# S88_Nano_16R0C_2Layers_DuPont.net
KiCad netlist of a schematic drawn in EAGLE
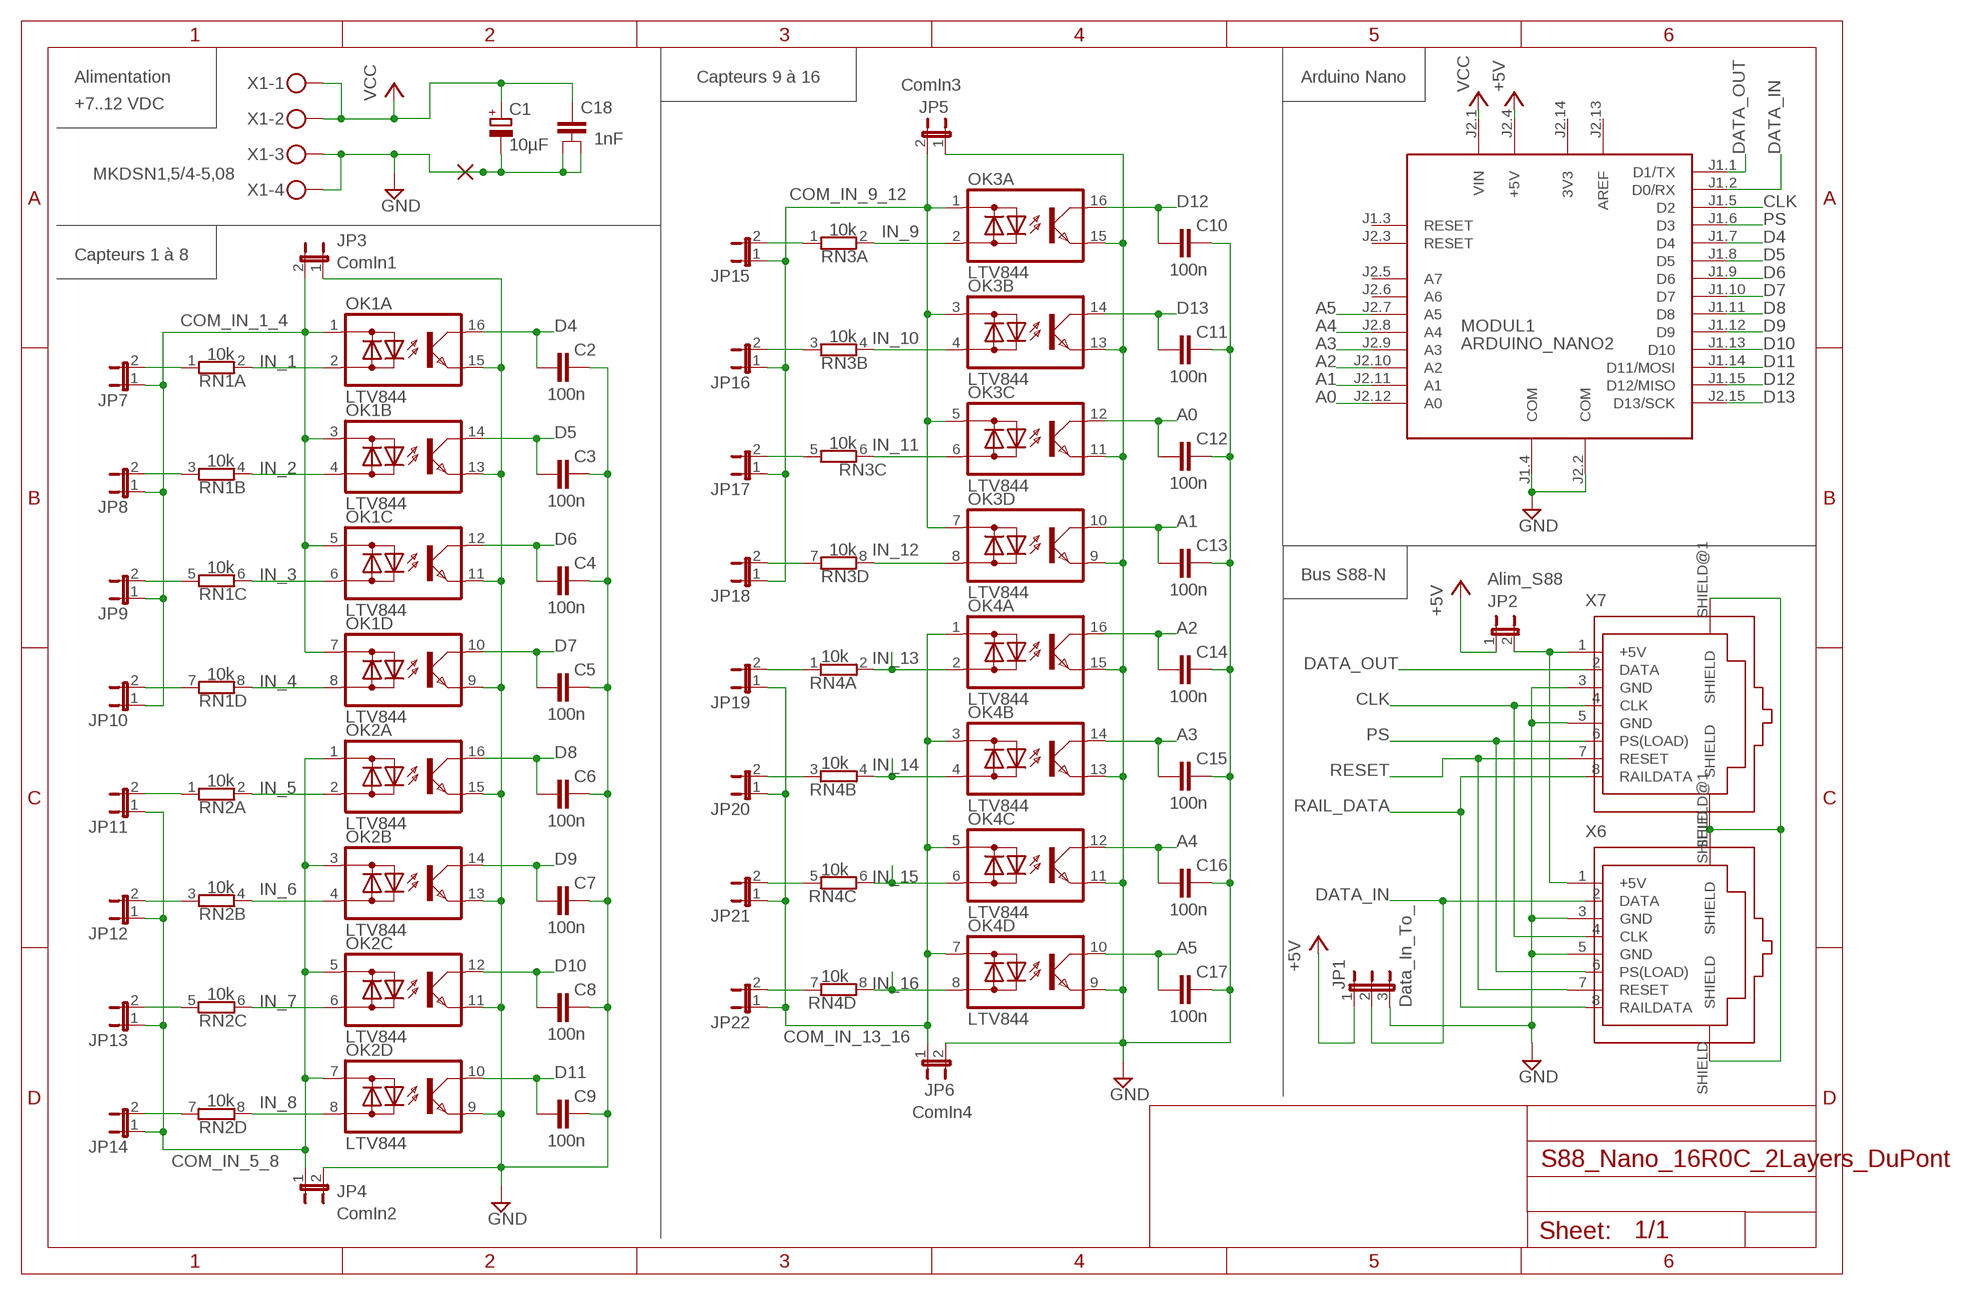
[diagram p0: schematic, sheet 1]

(export (version "E")
  (design (tool "Eeschema 10.0.6"))
  (components
    (comp (ref "C1")
      (value "10µF")
      (footprint "eagle-import:E5-6")
      (libsource (lib "eagle-import") (part "CPOL-EUE5-6"))
    )
    (comp (ref "C2")
      (value "100n")
      (footprint "eagle-import:C025-025X050")
      (libsource (lib "eagle-import") (part "C-EU025-025X050"))
    )
    (comp (ref "C3")
      (value "100n")
      (footprint "eagle-import:C025-025X050")
      (libsource (lib "eagle-import") (part "C-EU025-025X050"))
    )
    (comp (ref "C4")
      (value "100n")
      (footprint "eagle-import:C025-025X050")
      (libsource (lib "eagle-import") (part "C-EU025-025X050"))
    )
    (comp (ref "C5")
      (value "100n")
      (footprint "eagle-import:C025-025X050")
      (libsource (lib "eagle-import") (part "C-EU025-025X050"))
    )
    (comp (ref "C6")
      (value "100n")
      (footprint "eagle-import:C025-025X050")
      (libsource (lib "eagle-import") (part "C-EU025-025X050"))
    )
    (comp (ref "C7")
      (value "100n")
      (footprint "eagle-import:C025-025X050")
      (libsource (lib "eagle-import") (part "C-EU025-025X050"))
    )
    (comp (ref "C8")
      (value "100n")
      (footprint "eagle-import:C025-025X050")
      (libsource (lib "eagle-import") (part "C-EU025-025X050"))
    )
    (comp (ref "C9")
      (value "100n")
      (footprint "eagle-import:C025-025X050")
      (libsource (lib "eagle-import") (part "C-EU025-025X050"))
    )
    (comp (ref "C10")
      (value "100n")
      (footprint "eagle-import:C025-025X050")
      (libsource (lib "eagle-import") (part "C-EU025-025X050"))
    )
    (comp (ref "C11")
      (value "100n")
      (footprint "eagle-import:C025-025X050")
      (libsource (lib "eagle-import") (part "C-EU025-025X050"))
    )
    (comp (ref "C12")
      (value "100n")
      (footprint "eagle-import:C025-025X050")
      (libsource (lib "eagle-import") (part "C-EU025-025X050"))
    )
    (comp (ref "C13")
      (value "100n")
      (footprint "eagle-import:C025-025X050")
      (libsource (lib "eagle-import") (part "C-EU025-025X050"))
    )
    (comp (ref "C14")
      (value "100n")
      (footprint "eagle-import:C025-025X050")
      (libsource (lib "eagle-import") (part "C-EU025-025X050"))
    )
    (comp (ref "C15")
      (value "100n")
      (footprint "eagle-import:C025-025X050")
      (libsource (lib "eagle-import") (part "C-EU025-025X050"))
    )
    (comp (ref "C16")
      (value "100n")
      (footprint "eagle-import:C025-025X050")
      (libsource (lib "eagle-import") (part "C-EU025-025X050"))
    )
    (comp (ref "C17")
      (value "100n")
      (footprint "eagle-import:C025-025X050")
      (libsource (lib "eagle-import") (part "C-EU025-025X050"))
    )
    (comp (ref "C18")
      (value "1nF")
      (footprint "eagle-import:C025_050-024X070")
      (libsource (lib "eagle-import") (part "C-EU"))
    )
    (comp (ref "JP1")
      (value "Data_In_To_")
      (footprint "eagle-import:JP2")
      (libsource (lib "eagle-import") (part "JP2E"))
    )
    (comp (ref "JP2")
      (value "Alim_S88")
      (footprint "eagle-import:JP1")
      (libsource (lib "eagle-import") (part "JP1E"))
    )
    (comp (ref "JP3")
      (value "ComIn1")
      (footprint "eagle-import:JP1")
      (libsource (lib "eagle-import") (part "JP1E"))
    )
    (comp (ref "JP4")
      (value "ComIn2")
      (footprint "eagle-import:JP1")
      (libsource (lib "eagle-import") (part "JP1E"))
    )
    (comp (ref "JP5")
      (value "ComIn3")
      (footprint "eagle-import:JP1")
      (libsource (lib "eagle-import") (part "JP1E"))
    )
    (comp (ref "JP6")
      (value "ComIn4")
      (footprint "eagle-import:JP1")
      (libsource (lib "eagle-import") (part "JP1E"))
    )
    (comp (ref "JP7")
      (value "JP1E")
      (footprint "eagle-import:JP1")
      (libsource (lib "eagle-import") (part "jumper_252_JP1E"))
    )
    (comp (ref "JP8")
      (value "JP1E")
      (footprint "eagle-import:JP1")
      (libsource (lib "eagle-import") (part "jumper_252_JP1E"))
    )
    (comp (ref "JP9")
      (value "JP1E")
      (footprint "eagle-import:JP1")
      (libsource (lib "eagle-import") (part "jumper_252_JP1E"))
    )
    (comp (ref "JP10")
      (value "JP1E")
      (footprint "eagle-import:JP1")
      (libsource (lib "eagle-import") (part "jumper_252_JP1E"))
    )
    (comp (ref "JP11")
      (value "JP1E")
      (footprint "eagle-import:JP1")
      (libsource (lib "eagle-import") (part "jumper_252_JP1E"))
    )
    (comp (ref "JP12")
      (value "JP1E")
      (footprint "eagle-import:JP1")
      (libsource (lib "eagle-import") (part "jumper_252_JP1E"))
    )
    (comp (ref "JP13")
      (value "JP1E")
      (footprint "eagle-import:JP1")
      (libsource (lib "eagle-import") (part "jumper_252_JP1E"))
    )
    (comp (ref "JP14")
      (value "JP1E")
      (footprint "eagle-import:JP1")
      (libsource (lib "eagle-import") (part "jumper_252_JP1E"))
    )
    (comp (ref "JP15")
      (value "JP1E")
      (footprint "eagle-import:JP1")
      (libsource (lib "eagle-import") (part "jumper_252_JP1E"))
    )
    (comp (ref "JP16")
      (value "JP1E")
      (footprint "eagle-import:JP1")
      (libsource (lib "eagle-import") (part "jumper_252_JP1E"))
    )
    (comp (ref "JP17")
      (value "JP1E")
      (footprint "eagle-import:JP1")
      (libsource (lib "eagle-import") (part "jumper_252_JP1E"))
    )
    (comp (ref "JP18")
      (value "JP1E")
      (footprint "eagle-import:JP1")
      (libsource (lib "eagle-import") (part "jumper_252_JP1E"))
    )
    (comp (ref "JP19")
      (value "JP1E")
      (footprint "eagle-import:JP1")
      (libsource (lib "eagle-import") (part "jumper_252_JP1E"))
    )
    (comp (ref "JP20")
      (value "JP1E")
      (footprint "eagle-import:JP1")
      (libsource (lib "eagle-import") (part "jumper_252_JP1E"))
    )
    (comp (ref "JP21")
      (value "JP1E")
      (footprint "eagle-import:JP1")
      (libsource (lib "eagle-import") (part "jumper_252_JP1E"))
    )
    (comp (ref "JP22")
      (value "JP1E")
      (footprint "eagle-import:JP1")
      (libsource (lib "eagle-import") (part "jumper_252_JP1E"))
    )
    (comp (ref "MODUL1")
      (value "ARDUINO_NANO2")
      (footprint "eagle-import:ARDUINO_NANO2")
      (libsource (lib "eagle-import") (part "ARDUINO_NANO2"))
    )
    (comp (ref "OK1")
      (value "LTV844")
      (footprint "eagle-import:DIL16")
      (libsource (lib "eagle-import") (part "LTV844"))
    )
    (comp (ref "OK2")
      (value "LTV844")
      (footprint "eagle-import:DIL16")
      (libsource (lib "eagle-import") (part "LTV844"))
    )
    (comp (ref "OK3")
      (value "LTV844")
      (footprint "eagle-import:DIL16")
      (libsource (lib "eagle-import") (part "LTV844"))
    )
    (comp (ref "OK4")
      (value "LTV844")
      (footprint "eagle-import:DIL16")
      (libsource (lib "eagle-import") (part "LTV844"))
    )
    (comp (ref "PAD1")
      (value "1,9/0,8")
      (footprint "eagle-import:1,6_0,9")
      (libsource (lib "eagle-import") (part "1,9/0,8"))
    )
    (comp (ref "RN1")
      (value "10k")
      (footprint "eagle-import:SIL8")
      (libsource (lib "eagle-import") (part "E4R"))
    )
    (comp (ref "RN2")
      (value "10k")
      (footprint "eagle-import:SIL8")
      (libsource (lib "eagle-import") (part "E4R"))
    )
    (comp (ref "RN3")
      (value "10k")
      (footprint "eagle-import:SIL8")
      (libsource (lib "eagle-import") (part "E4R"))
    )
    (comp (ref "RN4")
      (value "10k")
      (footprint "eagle-import:SIL8")
      (libsource (lib "eagle-import") (part "E4R"))
    )
    (comp (ref "X1")
      (value "MKDSN1,5/4-5,08")
      (footprint "eagle-import:MKDSN1,5_4-5,08")
      (libsource (lib "eagle-import") (part "MKDSN1,5/4-5,08"))
    )
    (comp (ref "X6")
      (value "RJ45-SHIELDED")
      (footprint "eagle-import:RJ45-SHIELDED")
      (libsource (lib "eagle-import") (part "RJ45-SHIELDED"))
    )
    (comp (ref "X7")
      (value "RJ45-SHIELDED")
      (footprint "eagle-import:RJ45-SHIELDED")
      (libsource (lib "eagle-import") (part "RJ45-SHIELDED"))
    )
  )
  (nets
    (net (code "1") (name "+5V") (class "Default")
      (node (ref "JP1") (pin "1") (pinfunction "1_1") (pintype "passive"))
      (node (ref "JP2") (pin "1") (pinfunction "1_1") (pintype "passive"))
      (node (ref "MODUL1") (pin "J2.4") (pinfunction "+5V_J2.4") (pintype "power_in"))
    )
    (net (code "2") (name "/3V3") (class "Default")
      (node (ref "MODUL1") (pin "J2.14") (pinfunction "3V3_J2.14") (pintype "power_in"))
    )
    (net (code "3") (name "/A0") (class "Default")
      (node (ref "C12") (pin "1") (pinfunction "1_1") (pintype "passive"))
      (node (ref "MODUL1") (pin "J2.12") (pinfunction "A0_J2.12") (pintype "bidirectional"))
      (node (ref "OK3") (pin "12") (pinfunction "C_12") (pintype "passive"))
    )
    (net (code "4") (name "/A1") (class "Default")
      (node (ref "C13") (pin "1") (pinfunction "1_1") (pintype "passive"))
      (node (ref "MODUL1") (pin "J2.11") (pinfunction "A1_J2.11") (pintype "bidirectional"))
      (node (ref "OK3") (pin "10") (pinfunction "C_10") (pintype "passive"))
    )
    (net (code "5") (name "/A2") (class "Default")
      (node (ref "C14") (pin "1") (pinfunction "1_1") (pintype "passive"))
      (node (ref "MODUL1") (pin "J2.10") (pinfunction "A2_J2.10") (pintype "bidirectional"))
      (node (ref "OK4") (pin "16") (pinfunction "C_16") (pintype "passive"))
    )
    (net (code "6") (name "/A3") (class "Default")
      (node (ref "C15") (pin "1") (pinfunction "1_1") (pintype "passive"))
      (node (ref "MODUL1") (pin "J2.9") (pinfunction "A3_J2.9") (pintype "bidirectional"))
      (node (ref "OK4") (pin "14") (pinfunction "C_14") (pintype "passive"))
    )
    (net (code "7") (name "/A4") (class "Default")
      (node (ref "C16") (pin "1") (pinfunction "1_1") (pintype "passive"))
      (node (ref "MODUL1") (pin "J2.8") (pinfunction "A4_J2.8") (pintype "bidirectional"))
      (node (ref "OK4") (pin "12") (pinfunction "C_12") (pintype "passive"))
    )
    (net (code "8") (name "/A5") (class "Default")
      (node (ref "C17") (pin "1") (pinfunction "1_1") (pintype "passive"))
      (node (ref "MODUL1") (pin "J2.7") (pinfunction "A5_J2.7") (pintype "bidirectional"))
      (node (ref "OK4") (pin "10") (pinfunction "C_10") (pintype "passive"))
    )
    (net (code "9") (name "/AREF") (class "Default")
      (node (ref "MODUL1") (pin "J2.13") (pinfunction "AREF_J2.13") (pintype "power_in"))
    )
    (net (code "10") (name "/CLK") (class "Default")
      (node (ref "MODUL1") (pin "J1.5") (pinfunction "D2_J1.5") (pintype "bidirectional"))
      (node (ref "X6") (pin "4") (pinfunction "CLK_4") (pintype "bidirectional"))
      (node (ref "X7") (pin "4") (pinfunction "CLK_4") (pintype "bidirectional"))
    )
    (net (code "11") (name "/COM_IN_1_4") (class "Default")
      (node (ref "JP10") (pin "1") (pinfunction "1_1") (pintype "passive"))
      (node (ref "JP3") (pin "2") (pinfunction "2_2") (pintype "passive"))
      (node (ref "JP7") (pin "1") (pinfunction "1_1") (pintype "passive"))
      (node (ref "JP8") (pin "1") (pinfunction "1_1") (pintype "passive"))
      (node (ref "JP9") (pin "1") (pinfunction "1_1") (pintype "passive"))
      (node (ref "OK1") (pin "1") (pinfunction "AC1_1") (pintype "passive"))
      (node (ref "OK1") (pin "3") (pinfunction "AC1_3") (pintype "passive"))
      (node (ref "OK1") (pin "5") (pinfunction "AC1_5") (pintype "passive"))
      (node (ref "OK1") (pin "7") (pinfunction "AC1_7") (pintype "passive"))
    )
    (net (code "12") (name "/COM_IN_5_8") (class "Default")
      (node (ref "JP11") (pin "1") (pinfunction "1_1") (pintype "passive"))
      (node (ref "JP12") (pin "1") (pinfunction "1_1") (pintype "passive"))
      (node (ref "JP13") (pin "1") (pinfunction "1_1") (pintype "passive"))
      (node (ref "JP14") (pin "1") (pinfunction "1_1") (pintype "passive"))
      (node (ref "JP4") (pin "1") (pinfunction "1_1") (pintype "passive"))
      (node (ref "OK2") (pin "1") (pinfunction "AC1_1") (pintype "passive"))
      (node (ref "OK2") (pin "3") (pinfunction "AC1_3") (pintype "passive"))
      (node (ref "OK2") (pin "5") (pinfunction "AC1_5") (pintype "passive"))
      (node (ref "OK2") (pin "7") (pinfunction "AC1_7") (pintype "passive"))
    )
    (net (code "13") (name "/COM_IN_9_12") (class "Default")
      (node (ref "JP15") (pin "1") (pinfunction "1_1") (pintype "passive"))
      (node (ref "JP16") (pin "1") (pinfunction "1_1") (pintype "passive"))
      (node (ref "JP17") (pin "1") (pinfunction "1_1") (pintype "passive"))
      (node (ref "JP18") (pin "1") (pinfunction "1_1") (pintype "passive"))
      (node (ref "JP5") (pin "2") (pinfunction "2_2") (pintype "passive"))
      (node (ref "OK3") (pin "1") (pinfunction "AC1_1") (pintype "passive"))
      (node (ref "OK3") (pin "3") (pinfunction "AC1_3") (pintype "passive"))
      (node (ref "OK3") (pin "5") (pinfunction "AC1_5") (pintype "passive"))
      (node (ref "OK3") (pin "7") (pinfunction "AC1_7") (pintype "passive"))
    )
    (net (code "14") (name "/COM_IN_13_16") (class "Default")
      (node (ref "JP19") (pin "1") (pinfunction "1_1") (pintype "passive"))
      (node (ref "JP20") (pin "1") (pinfunction "1_1") (pintype "passive"))
      (node (ref "JP21") (pin "1") (pinfunction "1_1") (pintype "passive"))
      (node (ref "JP22") (pin "1") (pinfunction "1_1") (pintype "passive"))
      (node (ref "JP6") (pin "1") (pinfunction "1_1") (pintype "passive"))
      (node (ref "OK4") (pin "1") (pinfunction "AC1_1") (pintype "passive"))
      (node (ref "OK4") (pin "3") (pinfunction "AC1_3") (pintype "passive"))
      (node (ref "OK4") (pin "5") (pinfunction "AC1_5") (pintype "passive"))
      (node (ref "OK4") (pin "7") (pinfunction "AC1_7") (pintype "passive"))
    )
    (net (code "15") (name "/D4") (class "Default")
      (node (ref "C2") (pin "1") (pinfunction "1_1") (pintype "passive"))
      (node (ref "MODUL1") (pin "J1.7") (pinfunction "D4_J1.7") (pintype "bidirectional"))
      (node (ref "OK1") (pin "16") (pinfunction "C_16") (pintype "passive"))
    )
    (net (code "16") (name "/D5") (class "Default")
      (node (ref "C3") (pin "1") (pinfunction "1_1") (pintype "passive"))
      (node (ref "MODUL1") (pin "J1.8") (pinfunction "D5_J1.8") (pintype "bidirectional"))
      (node (ref "OK1") (pin "14") (pinfunction "C_14") (pintype "passive"))
    )
    (net (code "17") (name "/D6") (class "Default")
      (node (ref "C4") (pin "1") (pinfunction "1_1") (pintype "passive"))
      (node (ref "MODUL1") (pin "J1.9") (pinfunction "D6_J1.9") (pintype "bidirectional"))
      (node (ref "OK1") (pin "12") (pinfunction "C_12") (pintype "passive"))
    )
    (net (code "18") (name "/D7") (class "Default")
      (node (ref "C5") (pin "1") (pinfunction "1_1") (pintype "passive"))
      (node (ref "MODUL1") (pin "J1.10") (pinfunction "D7_J1.10") (pintype "bidirectional"))
      (node (ref "OK1") (pin "10") (pinfunction "C_10") (pintype "passive"))
    )
    (net (code "19") (name "/D8") (class "Default")
      (node (ref "C6") (pin "1") (pinfunction "1_1") (pintype "passive"))
      (node (ref "MODUL1") (pin "J1.11") (pinfunction "D8_J1.11") (pintype "bidirectional"))
      (node (ref "OK2") (pin "16") (pinfunction "C_16") (pintype "passive"))
    )
    (net (code "20") (name "/D9") (class "Default")
      (node (ref "C7") (pin "1") (pinfunction "1_1") (pintype "passive"))
      (node (ref "MODUL1") (pin "J1.12") (pinfunction "D9_J1.12") (pintype "bidirectional"))
      (node (ref "OK2") (pin "14") (pinfunction "C_14") (pintype "passive"))
    )
    (net (code "21") (name "/D10") (class "Default")
      (node (ref "C8") (pin "1") (pinfunction "1_1") (pintype "passive"))
      (node (ref "MODUL1") (pin "J1.13") (pinfunction "D10_J1.13") (pintype "bidirectional"))
      (node (ref "OK2") (pin "12") (pinfunction "C_12") (pintype "passive"))
    )
    (net (code "22") (name "/D11") (class "Default")
      (node (ref "C9") (pin "1") (pinfunction "1_1") (pintype "passive"))
      (node (ref "MODUL1") (pin "J1.14") (pinfunction "D11/MOSI_J1.14") (pintype "bidirectional"))
      (node (ref "OK2") (pin "10") (pinfunction "C_10") (pintype "passive"))
    )
    (net (code "23") (name "/D12") (class "Default")
      (node (ref "C10") (pin "1") (pinfunction "1_1") (pintype "passive"))
      (node (ref "MODUL1") (pin "J1.15") (pinfunction "D12/MISO_J1.15") (pintype "bidirectional"))
      (node (ref "OK3") (pin "16") (pinfunction "C_16") (pintype "passive"))
    )
    (net (code "24") (name "/D13") (class "Default")
      (node (ref "C11") (pin "1") (pinfunction "1_1") (pintype "passive"))
      (node (ref "MODUL1") (pin "J2.15") (pinfunction "D13/SCK_J2.15") (pintype "bidirectional"))
      (node (ref "OK3") (pin "14") (pinfunction "C_14") (pintype "passive"))
    )
    (net (code "25") (name "/DATA_IN") (class "Default")
      (node (ref "JP1") (pin "2") (pinfunction "2_2") (pintype "passive"))
      (node (ref "MODUL1") (pin "J1.2") (pinfunction "D0/RX_J1.2") (pintype "bidirectional"))
      (node (ref "X6") (pin "2") (pinfunction "DATA_2") (pintype "bidirectional"))
    )
    (net (code "26") (name "/DATA_OUT") (class "Default")
      (node (ref "MODUL1") (pin "J1.1") (pinfunction "D1/TX_J1.1") (pintype "bidirectional"))
      (node (ref "X7") (pin "2") (pinfunction "DATA_2") (pintype "bidirectional"))
    )
    (net (code "27") (name "/IN_1") (class "Default")
      (node (ref "OK1") (pin "2") (pinfunction "AC2_2") (pintype "passive"))
      (node (ref "RN1") (pin "2") (pinfunction "2_2") (pintype "passive"))
    )
    (net (code "28") (name "/IN_2") (class "Default")
      (node (ref "OK1") (pin "4") (pinfunction "AC2_4") (pintype "passive"))
      (node (ref "RN1") (pin "4") (pinfunction "2_4") (pintype "passive"))
    )
    (net (code "29") (name "/IN_3") (class "Default")
      (node (ref "OK1") (pin "6") (pinfunction "AC2_6") (pintype "passive"))
      (node (ref "RN1") (pin "6") (pinfunction "2_6") (pintype "passive"))
    )
    (net (code "30") (name "/IN_4") (class "Default")
      (node (ref "OK1") (pin "8") (pinfunction "AC2_8") (pintype "passive"))
      (node (ref "RN1") (pin "8") (pinfunction "2_8") (pintype "passive"))
    )
    (net (code "31") (name "/IN_5") (class "Default")
      (node (ref "OK2") (pin "2") (pinfunction "AC2_2") (pintype "passive"))
      (node (ref "RN2") (pin "2") (pinfunction "2_2") (pintype "passive"))
    )
    (net (code "32") (name "/IN_6") (class "Default")
      (node (ref "OK2") (pin "4") (pinfunction "AC2_4") (pintype "passive"))
      (node (ref "RN2") (pin "4") (pinfunction "2_4") (pintype "passive"))
    )
    (net (code "33") (name "/IN_7") (class "Default")
      (node (ref "OK2") (pin "6") (pinfunction "AC2_6") (pintype "passive"))
      (node (ref "RN2") (pin "6") (pinfunction "2_6") (pintype "passive"))
    )
    (net (code "34") (name "/IN_8") (class "Default")
      (node (ref "OK2") (pin "8") (pinfunction "AC2_8") (pintype "passive"))
      (node (ref "RN2") (pin "8") (pinfunction "2_8") (pintype "passive"))
    )
    (net (code "35") (name "/IN_9") (class "Default")
      (node (ref "OK3") (pin "2") (pinfunction "AC2_2") (pintype "passive"))
      (node (ref "RN3") (pin "2") (pinfunction "2_2") (pintype "passive"))
    )
    (net (code "36") (name "/IN_10") (class "Default")
      (node (ref "OK3") (pin "4") (pinfunction "AC2_4") (pintype "passive"))
      (node (ref "RN3") (pin "4") (pinfunction "2_4") (pintype "passive"))
    )
    (net (code "37") (name "/IN_11") (class "Default")
      (node (ref "OK3") (pin "6") (pinfunction "AC2_6") (pintype "passive"))
      (node (ref "RN3") (pin "6") (pinfunction "2_6") (pintype "passive"))
    )
    (net (code "38") (name "/IN_12") (class "Default")
      (node (ref "OK3") (pin "8") (pinfunction "AC2_8") (pintype "passive"))
      (node (ref "RN3") (pin "8") (pinfunction "2_8") (pintype "passive"))
    )
    (net (code "39") (name "/IN_13") (class "Default")
      (node (ref "OK4") (pin "2") (pinfunction "AC2_2") (pintype "passive"))
      (node (ref "RN4") (pin "2") (pinfunction "2_2") (pintype "passive"))
    )
    (net (code "40") (name "/IN_14") (class "Default")
      (node (ref "OK4") (pin "4") (pinfunction "AC2_4") (pintype "passive"))
      (node (ref "RN4") (pin "4") (pinfunction "2_4") (pintype "passive"))
    )
    (net (code "41") (name "/IN_15") (class "Default")
      (node (ref "OK4") (pin "6") (pinfunction "AC2_6") (pintype "passive"))
      (node (ref "RN4") (pin "6") (pinfunction "2_6") (pintype "passive"))
    )
    (net (code "42") (name "/IN_16") (class "Default")
      (node (ref "OK4") (pin "8") (pinfunction "AC2_8") (pintype "passive"))
      (node (ref "RN4") (pin "8") (pinfunction "2_8") (pintype "passive"))
    )
    (net (code "43") (name "/PS") (class "Default")
      (node (ref "MODUL1") (pin "J1.6") (pinfunction "D3_J1.6") (pintype "bidirectional"))
      (node (ref "X6") (pin "6") (pinfunction "PS(LOAD)_6") (pintype "bidirectional"))
      (node (ref "X7") (pin "6") (pinfunction "PS(LOAD)_6") (pintype "bidirectional"))
    )
    (net (code "44") (name "/RAIL_DATA") (class "Default")
      (node (ref "X6") (pin "8") (pinfunction "RAILDATA_8") (pintype "bidirectional"))
      (node (ref "X7") (pin "8") (pinfunction "RAILDATA_8") (pintype "bidirectional"))
    )
    (net (code "45") (name "/RESET") (class "Default")
      (node (ref "X6") (pin "7") (pinfunction "RESET_7") (pintype "bidirectional"))
      (node (ref "X7") (pin "7") (pinfunction "RESET_7") (pintype "bidirectional"))
    )
    (net (code "46") (name "GND") (class "Default")
      (node (ref "C1") (pin "-") (pinfunction "-_-") (pintype "passive"))
      (node (ref "C10") (pin "2") (pinfunction "2_2") (pintype "passive"))
      (node (ref "C11") (pin "2") (pinfunction "2_2") (pintype "passive"))
      (node (ref "C12") (pin "2") (pinfunction "2_2") (pintype "passive"))
      (node (ref "C13") (pin "2") (pinfunction "2_2") (pintype "passive"))
      (node (ref "C14") (pin "2") (pinfunction "2_2") (pintype "passive"))
      (node (ref "C15") (pin "2") (pinfunction "2_2") (pintype "passive"))
      (node (ref "C16") (pin "2") (pinfunction "2_2") (pintype "passive"))
      (node (ref "C17") (pin "2") (pinfunction "2_2") (pintype "passive"))
      (node (ref "C18") (pin "2") (pinfunction "2_2") (pintype "passive"))
      (node (ref "C18") (pin "3") (pinfunction "3_3") (pintype "passive"))
      (node (ref "C2") (pin "2") (pinfunction "2_2") (pintype "passive"))
      (node (ref "C3") (pin "2") (pinfunction "2_2") (pintype "passive"))
      (node (ref "C4") (pin "2") (pinfunction "2_2") (pintype "passive"))
      (node (ref "C5") (pin "2") (pinfunction "2_2") (pintype "passive"))
      (node (ref "C6") (pin "2") (pinfunction "2_2") (pintype "passive"))
      (node (ref "C7") (pin "2") (pinfunction "2_2") (pintype "passive"))
      (node (ref "C8") (pin "2") (pinfunction "2_2") (pintype "passive"))
      (node (ref "C9") (pin "2") (pinfunction "2_2") (pintype "passive"))
      (node (ref "JP1") (pin "3") (pinfunction "3_3") (pintype "passive"))
      (node (ref "JP3") (pin "1") (pinfunction "1_1") (pintype "passive"))
      (node (ref "JP4") (pin "2") (pinfunction "2_2") (pintype "passive"))
      (node (ref "JP5") (pin "1") (pinfunction "1_1") (pintype "passive"))
      (node (ref "JP6") (pin "2") (pinfunction "2_2") (pintype "passive"))
      (node (ref "MODUL1") (pin "J1.4") (pinfunction "COM_J1.4") (pintype "power_in"))
      (node (ref "MODUL1") (pin "J2.2") (pinfunction "COM_J2.2") (pintype "power_in"))
      (node (ref "OK1") (pin "11") (pinfunction "E_11") (pintype "passive"))
      (node (ref "OK1") (pin "13") (pinfunction "E_13") (pintype "passive"))
      (node (ref "OK1") (pin "15") (pinfunction "E_15") (pintype "passive"))
      (node (ref "OK1") (pin "9") (pinfunction "E_9") (pintype "passive"))
      (node (ref "OK2") (pin "11") (pinfunction "E_11") (pintype "passive"))
      (node (ref "OK2") (pin "13") (pinfunction "E_13") (pintype "passive"))
      (node (ref "OK2") (pin "15") (pinfunction "E_15") (pintype "passive"))
      (node (ref "OK2") (pin "9") (pinfunction "E_9") (pintype "passive"))
      (node (ref "OK3") (pin "11") (pinfunction "E_11") (pintype "passive"))
      (node (ref "OK3") (pin "13") (pinfunction "E_13") (pintype "passive"))
      (node (ref "OK3") (pin "15") (pinfunction "E_15") (pintype "passive"))
      (node (ref "OK3") (pin "9") (pinfunction "E_9") (pintype "passive"))
      (node (ref "OK4") (pin "11") (pinfunction "E_11") (pintype "passive"))
      (node (ref "OK4") (pin "13") (pinfunction "E_13") (pintype "passive"))
      (node (ref "OK4") (pin "15") (pinfunction "E_15") (pintype "passive"))
      (node (ref "OK4") (pin "9") (pinfunction "E_9") (pintype "passive"))
      (node (ref "PAD1") (pin "1") (pinfunction "P_1") (pintype "passive"))
      (node (ref "X1") (pin "3") (pinfunction "KL_3") (pintype "passive"))
      (node (ref "X1") (pin "4") (pinfunction "KL_4") (pintype "passive"))
      (node (ref "X6") (pin "3") (pinfunction "GND_3") (pintype "bidirectional"))
      (node (ref "X6") (pin "5") (pinfunction "GND_5") (pintype "bidirectional"))
      (node (ref "X7") (pin "3") (pinfunction "GND_3") (pintype "bidirectional"))
      (node (ref "X7") (pin "5") (pinfunction "GND_5") (pintype "bidirectional"))
    )
    (net (code "47") (name "Net-(JP7-Pad2)") (class "Default")
      (node (ref "JP7") (pin "2") (pinfunction "2_2") (pintype "passive"))
      (node (ref "RN1") (pin "1") (pinfunction "1_1") (pintype "passive"))
    )
    (net (code "48") (name "Net-(JP11-Pad2)") (class "Default")
      (node (ref "JP11") (pin "2") (pinfunction "2_2") (pintype "passive"))
      (node (ref "RN2") (pin "1") (pinfunction "1_1") (pintype "passive"))
    )
    (net (code "49") (name "Net-(JP15-Pad2)") (class "Default")
      (node (ref "JP15") (pin "2") (pinfunction "2_2") (pintype "passive"))
      (node (ref "RN3") (pin "1") (pinfunction "1_1") (pintype "passive"))
    )
    (net (code "50") (name "Net-(JP19-Pad2)") (class "Default")
      (node (ref "JP19") (pin "2") (pinfunction "2_2") (pintype "passive"))
      (node (ref "RN4") (pin "1") (pinfunction "1_1") (pintype "passive"))
    )
    (net (code "51") (name "Net-(RN1B-1)") (class "Default")
      (node (ref "JP8") (pin "2") (pinfunction "2_2") (pintype "passive"))
      (node (ref "RN1") (pin "3") (pinfunction "1_3") (pintype "passive"))
    )
    (net (code "52") (name "Net-(RN1C-1)") (class "Default")
      (node (ref "JP9") (pin "2") (pinfunction "2_2") (pintype "passive"))
      (node (ref "RN1") (pin "5") (pinfunction "1_5") (pintype "passive"))
    )
    (net (code "53") (name "Net-(RN1D-1)") (class "Default")
      (node (ref "JP10") (pin "2") (pinfunction "2_2") (pintype "passive"))
      (node (ref "RN1") (pin "7") (pinfunction "1_7") (pintype "passive"))
    )
    (net (code "54") (name "Net-(RN2B-1)") (class "Default")
      (node (ref "JP12") (pin "2") (pinfunction "2_2") (pintype "passive"))
      (node (ref "RN2") (pin "3") (pinfunction "1_3") (pintype "passive"))
    )
    (net (code "55") (name "Net-(RN2C-1)") (class "Default")
      (node (ref "JP13") (pin "2") (pinfunction "2_2") (pintype "passive"))
      (node (ref "RN2") (pin "5") (pinfunction "1_5") (pintype "passive"))
    )
    (net (code "56") (name "Net-(RN2D-1)") (class "Default")
      (node (ref "JP14") (pin "2") (pinfunction "2_2") (pintype "passive"))
      (node (ref "RN2") (pin "7") (pinfunction "1_7") (pintype "passive"))
    )
    (net (code "57") (name "Net-(RN3B-1)") (class "Default")
      (node (ref "JP16") (pin "2") (pinfunction "2_2") (pintype "passive"))
      (node (ref "RN3") (pin "3") (pinfunction "1_3") (pintype "passive"))
    )
    (net (code "58") (name "Net-(RN3C-1)") (class "Default")
      (node (ref "JP17") (pin "2") (pinfunction "2_2") (pintype "passive"))
      (node (ref "RN3") (pin "5") (pinfunction "1_5") (pintype "passive"))
    )
    (net (code "59") (name "Net-(RN3D-1)") (class "Default")
      (node (ref "JP18") (pin "2") (pinfunction "2_2") (pintype "passive"))
      (node (ref "RN3") (pin "7") (pinfunction "1_7") (pintype "passive"))
    )
    (net (code "60") (name "Net-(RN4B-1)") (class "Default")
      (node (ref "JP20") (pin "2") (pinfunction "2_2") (pintype "passive"))
      (node (ref "RN4") (pin "3") (pinfunction "1_3") (pintype "passive"))
    )
    (net (code "61") (name "Net-(RN4C-1)") (class "Default")
      (node (ref "JP21") (pin "2") (pinfunction "2_2") (pintype "passive"))
      (node (ref "RN4") (pin "5") (pinfunction "1_5") (pintype "passive"))
    )
    (net (code "62") (name "Net-(RN4D-1)") (class "Default")
      (node (ref "JP22") (pin "2") (pinfunction "2_2") (pintype "passive"))
      (node (ref "RN4") (pin "7") (pinfunction "1_7") (pintype "passive"))
    )
    (net (code "63") (name "Net-(X6-+5V)") (class "Default")
      (node (ref "JP2") (pin "2") (pinfunction "2_2") (pintype "passive"))
      (node (ref "X6") (pin "1") (pinfunction "+5V_1") (pintype "bidirectional"))
      (node (ref "X7") (pin "1") (pinfunction "+5V_1") (pintype "bidirectional"))
    )
    (net (code "64") (name "Net-(X6-PadSHIELD)") (class "Default")
      (node (ref "X6") (pin "SHIELD") (pinfunction "SHIELD_SHIELD") (pintype "power_in"))
      (node (ref "X6") (pin "SHIELD@1") (pinfunction "SHIELD_SHIELD@1") (pintype "power_in"))
      (node (ref "X7") (pin "SHIELD") (pinfunction "SHIELD_SHIELD") (pintype "power_in"))
      (node (ref "X7") (pin "SHIELD@1") (pinfunction "SHIELD_SHIELD@1") (pintype "power_in"))
    )
    (net (code "65") (name "VCC") (class "Default")
      (node (ref "C1") (pin "+") (pinfunction "+_+") (pintype "passive"))
      (node (ref "C18") (pin "1") (pinfunction "1_1") (pintype "passive"))
      (node (ref "MODUL1") (pin "J2.1") (pinfunction "VIN_J2.1") (pintype "power_in"))
      (node (ref "X1") (pin "1") (pinfunction "KL_1") (pintype "passive"))
      (node (ref "X1") (pin "2") (pinfunction "KL_2") (pintype "passive"))
    )
    (net (code "66") (name "unconnected-(MODUL1-A6-PadJ2.6)") (class "Default")
      (node (ref "MODUL1") (pin "J2.6") (pinfunction "A6_J2.6") (pintype "bidirectional"))
    )
    (net (code "67") (name "unconnected-(MODUL1-A7-PadJ2.5)") (class "Default")
      (node (ref "MODUL1") (pin "J2.5") (pinfunction "A7_J2.5") (pintype "bidirectional"))
    )
    (net (code "68") (name "unconnected-(MODUL1-RESET-PadJ1.3)") (class "Default")
      (node (ref "MODUL1") (pin "J1.3") (pinfunction "RESET_J1.3") (pintype "bidirectional"))
    )
    (net (code "69") (name "unconnected-(MODUL1-RESET-PadJ2.3)") (class "Default")
      (node (ref "MODUL1") (pin "J2.3") (pinfunction "RESET_J2.3") (pintype "bidirectional"))
    )
  )
)
